# FET__Converter.net
KiCad netlist of a schematic drawn in Altium Designer
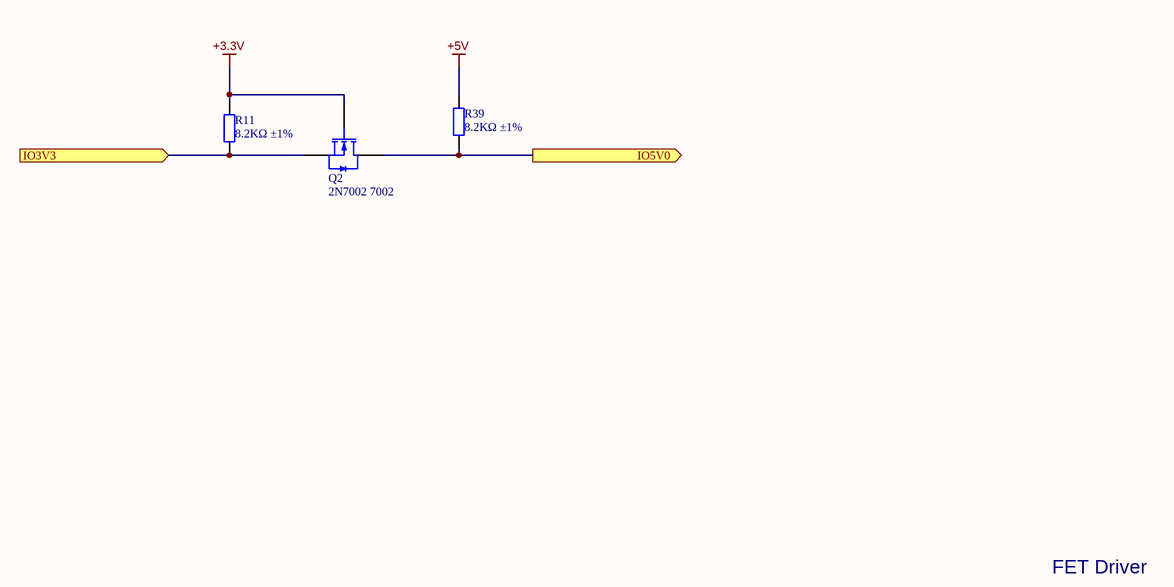
[diagram p0: FET__Converter.SchDoc]

(export (version "E")
  (design (tool "Eeschema 10.0.6"))
  (components
    (comp (ref "Q2")
      (value "2N7002 7002")
      (footprint "SOT-23(SOT-23-3)")
      (description "MOS(场效应管)")
      (libsource (lib "MOS") (part "2N7002 7002"))
    )
    (comp (ref "R11")
      (value "8.2KΩ ±1%")
      (footprint "0402_R")
      (description "Chip resistor")
      (fields (field (name "MANUFACTURER") "Uniroyal Elec") (field (name "PARTNUMBER") "0402WGF8201TCE"))
      (libsource (lib "RES") (part "0402 8.2K (8201) 1%"))
    )
    (comp (ref "R39")
      (value "8.2KΩ ±1%")
      (footprint "0402_R")
      (description "Chip resistor")
      (fields (field (name "MANUFACTURER") "Uniroyal Elec") (field (name "PARTNUMBER") "0402WGF8201TCE"))
      (libsource (lib "RES") (part "0402 8.2K (8201) 1%"))
    )
  )
  (nets
    (net (code "1") (name "+3.3V") (class "Default")
      (node (ref "Q2") (pin "1") (pinfunction "G_1") (pintype "passive"))
      (node (ref "R11") (pin "2") (pinfunction "2_2") (pintype "passive"))
    )
    (net (code "2") (name "+5V") (class "Default")
      (node (ref "R39") (pin "2") (pinfunction "2_2") (pintype "passive"))
    )
    (net (code "3") (name "/IO3V3") (class "Default")
      (node (ref "Q2") (pin "2") (pinfunction "S_2") (pintype "passive"))
      (node (ref "R11") (pin "1") (pinfunction "1_1") (pintype "passive"))
    )
    (net (code "4") (name "/IO5V0") (class "Default")
      (node (ref "Q2") (pin "3") (pinfunction "D_3") (pintype "passive"))
      (node (ref "R39") (pin "1") (pinfunction "1_1") (pintype "passive"))
    )
  )
)
